# Sensor_Box_CAN_Shutter_CTRL_STM.net
KiCad netlist of a schematic drawn in Altium Designer
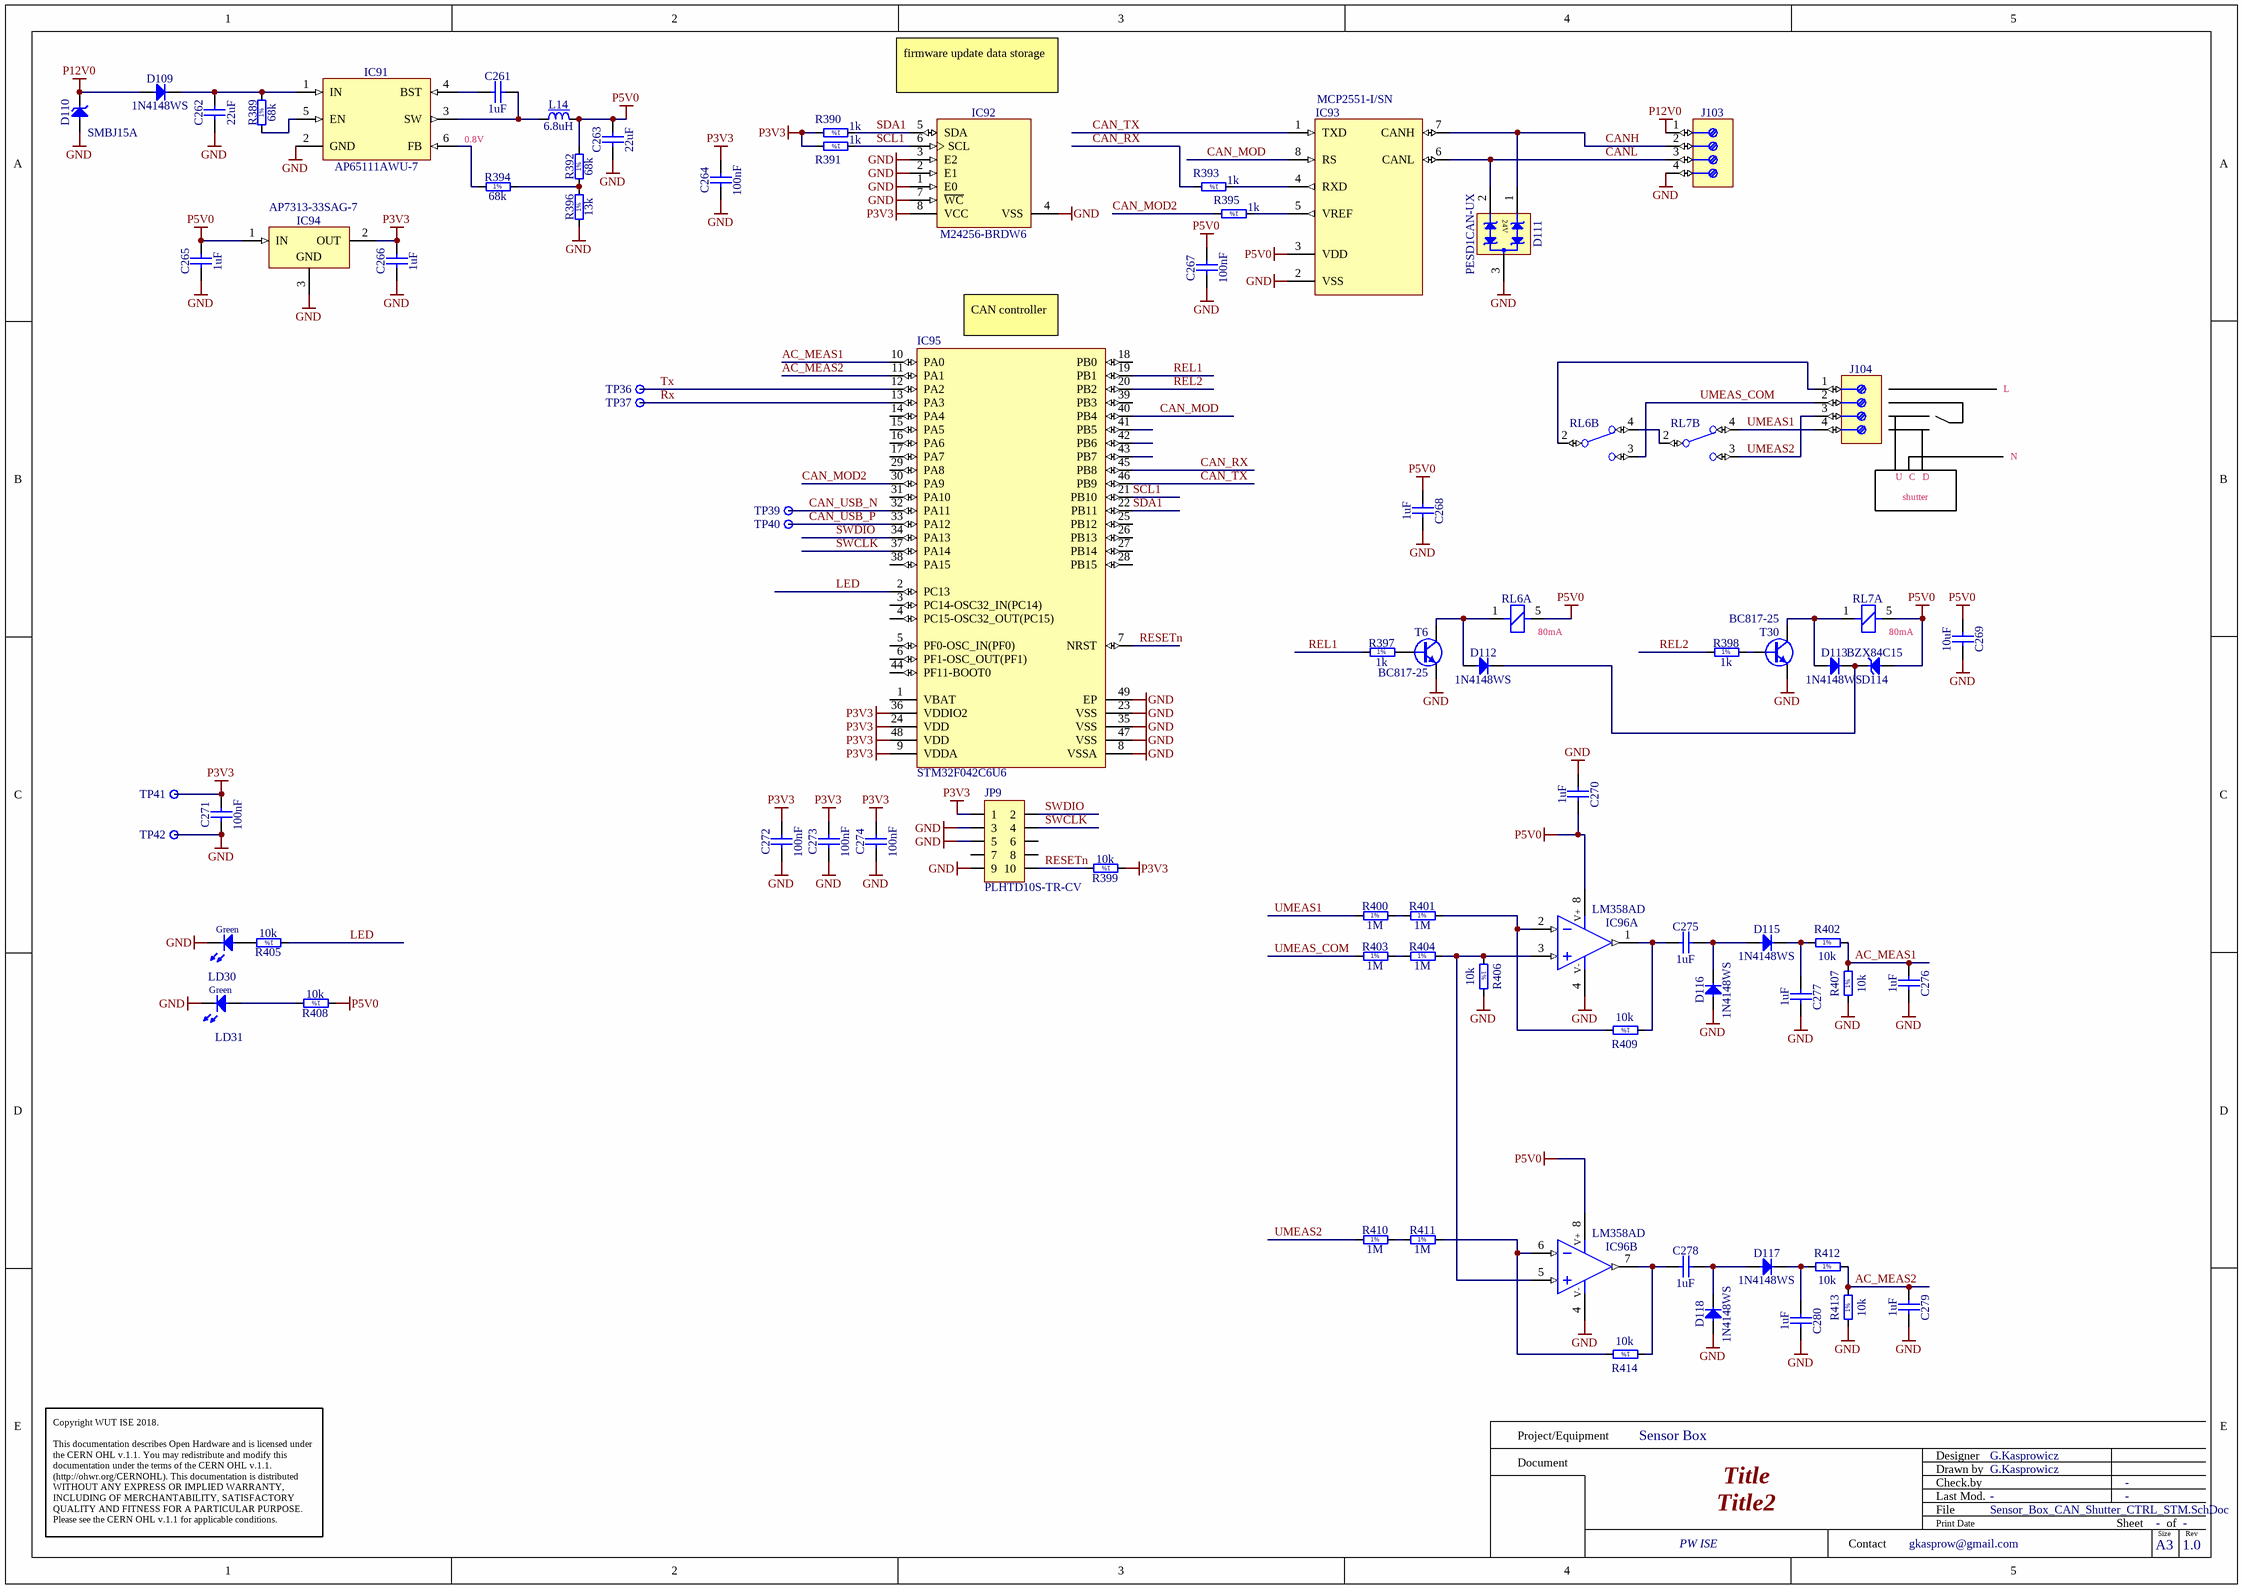
[diagram p0: Sensor_Box_CAN_Shutter_CTRL_STM.SchDoc]

(export (version "E")
  (design (tool "Eeschema 10.0.6"))
  (components
    (comp (ref "C261")
      (value "1uF")
      (footprint "CAPC1005X55N")
      (description "Non-polarised capacitor")
      (fields
        (field (name "PART NUMBER") "CC0402_1UF_16V_10%_X5R")
        (field (name "VOLTAGE") "16V")
        (field (name "AUTHOR") "CERN DEM JLC")
      )
      (libsource (lib "Capacitors") (part "Capacitor - non polarized"))
    )
    (comp (ref "C262")
      (value "22uF")
      (footprint "CAPC1709X100N")
      (description "Non-polarised capacitor")
      (fields
        (field (name "PART NUMBER") "CC0603_22UF_6.3V_20%_X5R")
        (field (name "VOLTAGE") "6.3V")
        (field (name "AUTHOR") "CERN DEM JLC")
      )
      (libsource (lib "Capacitors") (part "Capacitor - non polarized"))
    )
    (comp (ref "C263")
      (value "22uF")
      (footprint "CAPC1709X100N")
      (description "Non-polarised capacitor")
      (fields
        (field (name "PART NUMBER") "CC0603_22UF_6.3V_20%_X5R")
        (field (name "VOLTAGE") "6.3V")
        (field (name "AUTHOR") "CERN DEM JLC")
      )
      (libsource (lib "Capacitors") (part "Capacitor - non polarized"))
    )
    (comp (ref "C264")
      (value "100nF")
      (footprint "CAPC1005X55N")
      (description "Non-polarised capacitor")
      (fields
        (field (name "PART NUMBER") "CC0402_100NF_16V_10%_X5R")
        (field (name "VOLTAGE") "16V")
        (field (name "AUTHOR") "CERN DEM JLC")
      )
      (libsource (lib "Capacitors") (part "Capacitor - non polarized"))
    )
    (comp (ref "C265")
      (value "1uF")
      (footprint "CAPC1005X55N")
      (description "Non-polarised capacitor")
      (fields
        (field (name "PART NUMBER") "CC0402_1UF_16V_10%_X5R")
        (field (name "VOLTAGE") "16V")
        (field (name "AUTHOR") "CERN DEM JLC")
      )
      (libsource (lib "Capacitors") (part "Capacitor - non polarized"))
    )
    (comp (ref "C266")
      (value "1uF")
      (footprint "CAPC1005X55N")
      (description "Non-polarised capacitor")
      (fields
        (field (name "PART NUMBER") "CC0402_1UF_16V_10%_X5R")
        (field (name "VOLTAGE") "16V")
        (field (name "AUTHOR") "CERN DEM JLC")
      )
      (libsource (lib "Capacitors") (part "Capacitor - non polarized"))
    )
    (comp (ref "C267")
      (value "100nF")
      (footprint "CAPC1005X55N")
      (description "Non-polarised capacitor")
      (fields
        (field (name "PART NUMBER") "CC0402_100NF_16V_10%_X5R")
        (field (name "VOLTAGE") "16V")
        (field (name "AUTHOR") "CERN DEM JLC")
      )
      (libsource (lib "Capacitors") (part "Capacitor - non polarized"))
    )
    (comp (ref "C268")
      (value "1uF")
      (footprint "CAPC1005X55N")
      (description "Non-polarised capacitor")
      (fields
        (field (name "PART NUMBER") "CC0402_1UF_16V_10%_X5R")
        (field (name "VOLTAGE") "16V")
        (field (name "AUTHOR") "CERN DEM JLC")
      )
      (libsource (lib "Capacitors") (part "Capacitor - non polarized"))
    )
    (comp (ref "C269")
      (value "10uF")
      (footprint "CAPC2012X135N")
      (description "Non-polarised capacitor")
      (fields
        (field (name "PART NUMBER") "CC0805_10UF_16V_10%_X5R")
        (field (name "VOLTAGE") "16V")
        (field (name "AUTHOR") "CERN DEM JLC")
      )
      (libsource (lib "Capacitors") (part "Capacitor - non polarized"))
    )
    (comp (ref "C270")
      (value "1uF")
      (footprint "CAPC1005X55N")
      (description "Non-polarised capacitor")
      (fields
        (field (name "PART NUMBER") "CC0402_1UF_16V_10%_X5R")
        (field (name "VOLTAGE") "16V")
        (field (name "AUTHOR") "CERN DEM JLC")
      )
      (libsource (lib "Capacitors") (part "Capacitor - non polarized"))
    )
    (comp (ref "C271")
      (value "100nF")
      (footprint "CAPC1005X55N")
      (description "Non-polarised capacitor")
      (fields
        (field (name "PART NUMBER") "CC0402_100NF_16V_10%_X5R")
        (field (name "VOLTAGE") "16V")
        (field (name "AUTHOR") "CERN DEM JLC")
      )
      (libsource (lib "Capacitors") (part "Capacitor - non polarized"))
    )
    (comp (ref "C272")
      (value "100nF")
      (footprint "CAPC1005X55N")
      (description "Non-polarised capacitor")
      (fields
        (field (name "PART NUMBER") "CC0402_100NF_16V_10%_X5R")
        (field (name "VOLTAGE") "16V")
        (field (name "AUTHOR") "CERN DEM JLC")
      )
      (libsource (lib "Capacitors") (part "Capacitor - non polarized"))
    )
    (comp (ref "C273")
      (value "100nF")
      (footprint "CAPC1005X55N")
      (description "Non-polarised capacitor")
      (fields
        (field (name "PART NUMBER") "CC0402_100NF_16V_10%_X5R")
        (field (name "VOLTAGE") "16V")
        (field (name "AUTHOR") "CERN DEM JLC")
      )
      (libsource (lib "Capacitors") (part "Capacitor - non polarized"))
    )
    (comp (ref "C274")
      (value "100nF")
      (footprint "CAPC1005X55N")
      (description "Non-polarised capacitor")
      (fields
        (field (name "PART NUMBER") "CC0402_100NF_16V_10%_X5R")
        (field (name "VOLTAGE") "16V")
        (field (name "AUTHOR") "CERN DEM JLC")
      )
      (libsource (lib "Capacitors") (part "Capacitor - non polarized"))
    )
    (comp (ref "C275")
      (value "1uF")
      (footprint "CAPC1005X55N")
      (description "Non-polarised capacitor")
      (fields
        (field (name "PART NUMBER") "CC0402_1UF_16V_10%_X5R")
        (field (name "VOLTAGE") "16V")
        (field (name "AUTHOR") "CERN DEM JLC")
      )
      (libsource (lib "Capacitors") (part "Capacitor - non polarized"))
    )
    (comp (ref "C276")
      (value "1uF")
      (footprint "CAPC1005X55N")
      (description "Non-polarised capacitor")
      (fields
        (field (name "PART NUMBER") "CC0402_1UF_16V_10%_X5R")
        (field (name "VOLTAGE") "16V")
        (field (name "AUTHOR") "CERN DEM JLC")
      )
      (libsource (lib "Capacitors") (part "Capacitor - non polarized"))
    )
    (comp (ref "C277")
      (value "1uF")
      (footprint "CAPC1005X55N")
      (description "Non-polarised capacitor")
      (fields
        (field (name "PART NUMBER") "CC0402_1UF_16V_10%_X5R")
        (field (name "VOLTAGE") "16V")
        (field (name "AUTHOR") "CERN DEM JLC")
      )
      (libsource (lib "Capacitors") (part "Capacitor - non polarized"))
    )
    (comp (ref "C278")
      (value "1uF")
      (footprint "CAPC1005X55N")
      (description "Non-polarised capacitor")
      (fields
        (field (name "PART NUMBER") "CC0402_1UF_16V_10%_X5R")
        (field (name "VOLTAGE") "16V")
        (field (name "AUTHOR") "CERN DEM JLC")
      )
      (libsource (lib "Capacitors") (part "Capacitor - non polarized"))
    )
    (comp (ref "C279")
      (value "1uF")
      (footprint "CAPC1005X55N")
      (description "Non-polarised capacitor")
      (fields
        (field (name "PART NUMBER") "CC0402_1UF_16V_10%_X5R")
        (field (name "VOLTAGE") "16V")
        (field (name "AUTHOR") "CERN DEM JLC")
      )
      (libsource (lib "Capacitors") (part "Capacitor - non polarized"))
    )
    (comp (ref "C280")
      (value "1uF")
      (footprint "CAPC1005X55N")
      (description "Non-polarised capacitor")
      (fields
        (field (name "PART NUMBER") "CC0402_1UF_16V_10%_X5R")
        (field (name "VOLTAGE") "16V")
        (field (name "AUTHOR") "CERN DEM JLC")
      )
      (libsource (lib "Capacitors") (part "Capacitor - non polarized"))
    )
    (comp (ref "D109")
      (value "1N4148WS")
      (footprint "SODFL2512X100N")
      (description "Diode")
      (fields
        (field (name "VOLTAGE") "75V")
        (field (name "POWER") "150mA")
        (field (name "AUTHOR") "CERN DEM JLC")
      )
      (libsource (lib "ICs And Semiconductors") (part "Diode"))
    )
    (comp (ref "D110")
      (value "SMBJ15A")
      (footprint "DIOM5336X265N")
      (description "Zener Diode")
      (fields
        (field (name "VOLTAGE") "15V")
        (field (name "POWER") "600W")
        (field (name "AUTHOR") "CERN DEM JLC")
      )
      (libsource (lib "ICs And Semiconductors") (part "Diode Zener"))
    )
    (comp (ref "D111")
      (value "PESD1CAN-UX")
      (footprint "SOT95P237X112-3N")
      (description "TVS Diode for CAN")
      (fields
        (field (name "VOLTAGE") "24V")
        (field (name "POWER") "400W")
        (field (name "AUTHOR") "CERN DEM JLC")
      )
      (libsource (lib "LIBRARY_SCH") (part "D_TVS_PESD1CAN"))
    )
    (comp (ref "D112")
      (value "1N4148WS")
      (footprint "SODFL2512X100N")
      (description "Diode")
      (fields
        (field (name "VOLTAGE") "75V")
        (field (name "POWER") "150mA")
        (field (name "AUTHOR") "CERN DEM JLC")
      )
      (libsource (lib "ICs And Semiconductors") (part "Diode"))
    )
    (comp (ref "D113")
      (value "1N4148WS")
      (footprint "SODFL2512X100N")
      (description "Diode")
      (fields
        (field (name "VOLTAGE") "75V")
        (field (name "POWER") "150mA")
        (field (name "AUTHOR") "CERN DEM JLC")
      )
      (libsource (lib "ICs And Semiconductors") (part "Diode"))
    )
    (comp (ref "D114")
      (value "BZX84C15")
      (footprint "SOT95P240X130-3N")
      (description "Diode Zener Anode Pin 1 Cathode Pin 3 (Pas de pin 2)")
      (fields
        (field (name "VOLTAGE") "15V")
        (field (name "POWER") "350mW")
        (field (name "AUTHOR") "CERN DEM JLC")
      )
      (libsource (lib "ICs And Semiconductors") (part "Diode Zener A1C3"))
    )
    (comp (ref "D115")
      (value "1N4148WS")
      (footprint "SODFL2512X100N")
      (description "Diode")
      (fields
        (field (name "VOLTAGE") "75V")
        (field (name "POWER") "150mA")
        (field (name "AUTHOR") "CERN DEM JLC")
      )
      (libsource (lib "ICs And Semiconductors") (part "Diode"))
    )
    (comp (ref "D116")
      (value "1N4148WS")
      (footprint "SODFL2512X100N")
      (description "Diode")
      (fields
        (field (name "VOLTAGE") "75V")
        (field (name "POWER") "150mA")
        (field (name "AUTHOR") "CERN DEM JLC")
      )
      (libsource (lib "ICs And Semiconductors") (part "Diode"))
    )
    (comp (ref "D117")
      (value "1N4148WS")
      (footprint "SODFL2512X100N")
      (description "Diode")
      (fields
        (field (name "VOLTAGE") "75V")
        (field (name "POWER") "150mA")
        (field (name "AUTHOR") "CERN DEM JLC")
      )
      (libsource (lib "ICs And Semiconductors") (part "Diode"))
    )
    (comp (ref "D118")
      (value "1N4148WS")
      (footprint "SODFL2512X100N")
      (description "Diode")
      (fields
        (field (name "VOLTAGE") "75V")
        (field (name "POWER") "150mA")
        (field (name "AUTHOR") "CERN DEM JLC")
      )
      (libsource (lib "ICs And Semiconductors") (part "Diode"))
    )
    (comp (ref "IC91")
      (value "AP65111AWU-7")
      (footprint "SOT95P280X100-6N")
      (description "Light Load Improved 1.5A Synch DC/DC Buck Converter")
      (fields (field (name "MANUFACTURER") "DIODES INCORPORATED") (field (name "AUTHOR") "CERN DEM JLC"))
      (libsource (lib "ICs And Semiconductors") (part "AP65111A"))
    )
    (comp (ref "IC92")
      (value "M24256-BRDW6")
      (footprint "SOP65P640X120-8N")
      (description "256-Kbit Serial I²C Bus EEPROM")
      (fields
        (field (name "PART NUMBER") "M24256-BRDW6P")
        (field (name "MANUFACTURER") "ST MICROELECTRONICS")
        (field (name "AUTHOR") "CERN DEM MR")
      )
      (libsource (lib "LIBRARY_SCH") (part "MEM_M24256-BRDW6P"))
    )
    (comp (ref "IC93")
      (value "MCP2551-I/SN")
      (footprint "SOIC127P600X175-8N")
      (description "High-Speed CAN Transceiver, 8-Pin SOIC, Industrial Temperature")
      (fields (field (name "MANUFACTURER") "MICROCHIP TECHNOLOGY") (field (name "AUTHOR") "GK"))
      (libsource (lib "LIBRARY_SCH") (part "IFC_MCP2551"))
    )
    (comp (ref "IC94")
      (value "AP7313-33SAG-7")
      (footprint "SOT95P240X130-3N")
      (description "3-Terminal Regulator 1=IN 2=OUT 3=GND")
      (fields (field (name "MANUFACTURER") "DIODES INCORPORATED") (field (name "AUTHOR") "CERN DEM JLC"))
      (libsource (lib "ICs And Semiconductors") (part "REG3 1IN-2OUT-3GND"))
    )
    (comp (ref "IC95")
      (value "STM32F042C6U6")
      (footprint "STM-UFQFPN48_L")
      (libsource (lib "Altium Content Vault") (part "MC-ARM-STM32F042-UFQFPN48"))
    )
    (comp (ref "IC96")
      (value "LM358AD")
      (footprint "SOIC127P600X175-8N")
      (description "Dual Operational Amplifier")
      (fields (field (name "MANUFACTURER") "TEXAS INSTRUMENTS") (field (name "AUTHOR") "CERN DEM JLC"))
      (libsource (lib "ICs And Semiconductors") (part "Operational Amplifier x2 Type1"))
    )
    (comp (ref "J103")
      (value "~")
      (footprint "PHOENIX_1725672")
      (description "Terminal Block, 4 Positions, Screw Connection")
      (fields
        (field (name "PART NUMBER") "PHOENIX_1725672")
        (field (name "MANUFACTURER") "PHOENIX CONTACT")
        (field (name "AUTHOR") "CERN DEM JMW")
      )
      (libsource (lib "Connectors") (part "Terminal Block_4 Positions_Screw Connection"))
    )
    (comp (ref "J104")
      (value "~")
      (footprint "TYCO_282836-4")
      (description "Terminal Block, 4 Positions, Screw Connection")
      (fields
        (field (name "PART NUMBER") "TYCO_282836-4")
        (field (name "MANUFACTURER") "TYCO ELECTRONICS")
        (field (name "AUTHOR") "CERN DEM JLC")
      )
      (libsource (lib "Connectors") (part "Terminal Block_4 Positions_Screw Connection"))
    )
    (comp (ref "JP9")
      (value "PLHTD10S-TR-CV")
      (footprint "PLHTD10S-TR-CV")
      (description "1.27 mm dual row goldpin (Maritex)")
      (libsource (lib "LIBRARY_SCH") (part "CON_2x5 1.27 SMT Male"))
    )
    (comp (ref "L14")
      (value "6.8uH")
      (footprint "IND_WALSIN_WLPN3030")
      (description "6,8uH; 900mA; 0,211Ω; 3x3x1,5mm")
      (fields
        (field (name "PART NUMBER") "IND_6.8UH_20%_WALSIN_WLPN303015M6R8PB")
        (field (name "POWER") "900mA")
        (field (name "AUTHOR") "GK")
      )
      (libsource (lib "LIBRARY_SCH") (part "IND_WLPN3030"))
    )
    (comp (ref "LD30")
      (value "Green")
      (footprint "LED_KINGBRIGHT_KPH-1608CGCK")
      (description "LED Green 1C 2A")
      (fields
        (field (name "PART NUMBER") "LED_KINGBRIGHT_KPH-1608CGCK")
        (field (name "MANUFACTURER") "KINGBRIGHT")
        (field (name "AUTHOR") "CERN DEM JLC")
      )
      (libsource (lib "ICs And Semiconductors") (part "LED Green 1C 2A"))
    )
    (comp (ref "LD31")
      (value "Green")
      (footprint "LED_KINGBRIGHT_KPH-1608CGCK")
      (description "LED Green 1C 2A")
      (fields
        (field (name "PART NUMBER") "LED_KINGBRIGHT_KPH-1608CGCK")
        (field (name "MANUFACTURER") "KINGBRIGHT")
        (field (name "AUTHOR") "CERN DEM JLC")
      )
      (libsource (lib "ICs And Semiconductors") (part "LED Green 1C 2A"))
    )
    (comp (ref "R389")
      (value "68k")
      (footprint "RESC1005X40N")
      (description "Resistor - 1%")
      (fields
        (field (name "PART NUMBER") "R0402_68K_1%_0.0625W_100PPM")
        (field (name "POWER") "0.0625W")
        (field (name "AUTHOR") "CERN DEM JLC")
      )
      (libsource (lib "Resistors") (part "Resistor - 1%"))
    )
    (comp (ref "R390")
      (value "1k")
      (footprint "RESC1005X40N")
      (description "Resistor - 1%")
      (fields
        (field (name "PART NUMBER") "R0402_1K_1%_0.0625W_100PPM")
        (field (name "POWER") "0.0625W")
        (field (name "AUTHOR") "CERN DEM JLC")
      )
      (libsource (lib "Resistors") (part "Resistor - 1%"))
    )
    (comp (ref "R391")
      (value "1k")
      (footprint "RESC1005X40N")
      (description "Resistor - 1%")
      (fields
        (field (name "PART NUMBER") "R0402_1K_1%_0.0625W_100PPM")
        (field (name "POWER") "0.0625W")
        (field (name "AUTHOR") "CERN DEM JLC")
      )
      (libsource (lib "Resistors") (part "Resistor - 1%"))
    )
    (comp (ref "R392")
      (value "68k")
      (footprint "RESC1005X40N")
      (description "Resistor - 1%")
      (fields
        (field (name "PART NUMBER") "R0402_68K_1%_0.0625W_100PPM")
        (field (name "POWER") "0.0625W")
        (field (name "AUTHOR") "CERN DEM JLC")
      )
      (libsource (lib "Resistors") (part "Resistor - 1%"))
    )
    (comp (ref "R393")
      (value "1k")
      (footprint "RESC1005X40N")
      (description "Resistor - 1%")
      (fields
        (field (name "PART NUMBER") "R0402_1K_1%_0.0625W_100PPM")
        (field (name "POWER") "0.0625W")
        (field (name "AUTHOR") "CERN DEM JLC")
      )
      (libsource (lib "Resistors") (part "Resistor - 1%"))
    )
    (comp (ref "R394")
      (value "68k")
      (footprint "RESC1005X40N")
      (description "Resistor - 1%")
      (fields
        (field (name "PART NUMBER") "R0402_68K_1%_0.0625W_100PPM")
        (field (name "POWER") "0.0625W")
        (field (name "AUTHOR") "CERN DEM JLC")
      )
      (libsource (lib "Resistors") (part "Resistor - 1%"))
    )
    (comp (ref "R395")
      (value "1k")
      (footprint "RESC1005X40N")
      (description "Resistor - 1%")
      (fields
        (field (name "PART NUMBER") "R0402_1K_1%_0.0625W_100PPM")
        (field (name "POWER") "0.0625W")
        (field (name "AUTHOR") "CERN DEM JLC")
      )
      (libsource (lib "Resistors") (part "Resistor - 1%"))
    )
    (comp (ref "R396")
      (value "13k")
      (footprint "RESC1005X40N")
      (description "Resistor - 1%")
      (fields
        (field (name "PART NUMBER") "R0402_13K_1%_0.0625W_100PPM")
        (field (name "POWER") "0.0625W")
        (field (name "AUTHOR") "CERN DEM JLC")
      )
      (libsource (lib "Resistors") (part "Resistor - 1%"))
    )
    (comp (ref "R397")
      (value "1k")
      (footprint "RESC1005X40N")
      (description "Resistor - 1%")
      (fields
        (field (name "PART NUMBER") "R0402_1K_1%_0.0625W_100PPM")
        (field (name "POWER") "0.0625W")
        (field (name "AUTHOR") "CERN DEM JLC")
      )
      (libsource (lib "Resistors") (part "Resistor - 1%"))
    )
    (comp (ref "R398")
      (value "1k")
      (footprint "RESC1005X40N")
      (description "Resistor - 1%")
      (fields
        (field (name "PART NUMBER") "R0402_1K_1%_0.0625W_100PPM")
        (field (name "POWER") "0.0625W")
        (field (name "AUTHOR") "CERN DEM JLC")
      )
      (libsource (lib "Resistors") (part "Resistor - 1%"))
    )
    (comp (ref "R399")
      (value "10k")
      (footprint "RESC1005X40N")
      (description "Resistor - 1%")
      (fields
        (field (name "PART NUMBER") "R0402_10K_1%_0.0625W_100PPM")
        (field (name "POWER") "0.0625W")
        (field (name "AUTHOR") "CERN DEM JLC")
      )
      (libsource (lib "Resistors") (part "Resistor - 1%"))
    )
    (comp (ref "R400")
      (value "1M")
      (footprint "RESC3216X65N")
      (description "Resistor - 1%")
      (fields
        (field (name "PART NUMBER") "R1206_1M_1%_0.25W_100PPM")
        (field (name "POWER") "0.25W")
        (field (name "AUTHOR") "CERN DEM JLC")
      )
      (libsource (lib "Resistors") (part "Resistor - 1%"))
    )
    (comp (ref "R401")
      (value "1M")
      (footprint "RESC3216X65N")
      (description "Resistor - 1%")
      (fields
        (field (name "PART NUMBER") "R1206_1M_1%_0.25W_100PPM")
        (field (name "POWER") "0.25W")
        (field (name "AUTHOR") "CERN DEM JLC")
      )
      (libsource (lib "Resistors") (part "Resistor - 1%"))
    )
    (comp (ref "R402")
      (value "10k")
      (footprint "RESC1005X40N")
      (description "Resistor - 1%")
      (fields
        (field (name "PART NUMBER") "R0402_10K_1%_0.0625W_100PPM")
        (field (name "POWER") "0.0625W")
        (field (name "AUTHOR") "CERN DEM JLC")
      )
      (libsource (lib "Resistors") (part "Resistor - 1%"))
    )
    (comp (ref "R403")
      (value "1M")
      (footprint "RESC3216X65N")
      (description "Resistor - 1%")
      (fields
        (field (name "PART NUMBER") "R1206_1M_1%_0.25W_100PPM")
        (field (name "POWER") "0.25W")
        (field (name "AUTHOR") "CERN DEM JLC")
      )
      (libsource (lib "Resistors") (part "Resistor - 1%"))
    )
    (comp (ref "R404")
      (value "1M")
      (footprint "RESC3216X65N")
      (description "Resistor - 1%")
      (fields
        (field (name "PART NUMBER") "R1206_1M_1%_0.25W_100PPM")
        (field (name "POWER") "0.25W")
        (field (name "AUTHOR") "CERN DEM JLC")
      )
      (libsource (lib "Resistors") (part "Resistor - 1%"))
    )
    (comp (ref "R405")
      (value "10k")
      (footprint "RESC1005X40N")
      (description "Resistor - 1%")
      (fields
        (field (name "PART NUMBER") "R0402_10K_1%_0.0625W_100PPM")
        (field (name "POWER") "0.0625W")
        (field (name "AUTHOR") "CERN DEM JLC")
      )
      (libsource (lib "Resistors") (part "Resistor - 1%"))
    )
    (comp (ref "R406")
      (value "10k")
      (footprint "RESC1005X40N")
      (description "Resistor - 1%")
      (fields
        (field (name "PART NUMBER") "R0402_10K_1%_0.0625W_100PPM")
        (field (name "POWER") "0.0625W")
        (field (name "AUTHOR") "CERN DEM JLC")
      )
      (libsource (lib "Resistors") (part "Resistor - 1%"))
    )
    (comp (ref "R407")
      (value "10k")
      (footprint "RESC1005X40N")
      (description "Resistor - 1%")
      (fields
        (field (name "PART NUMBER") "R0402_10K_1%_0.0625W_100PPM")
        (field (name "POWER") "0.0625W")
        (field (name "AUTHOR") "CERN DEM JLC")
      )
      (libsource (lib "Resistors") (part "Resistor - 1%"))
    )
    (comp (ref "R408")
      (value "10k")
      (footprint "RESC1005X40N")
      (description "Resistor - 1%")
      (fields
        (field (name "PART NUMBER") "R0402_10K_1%_0.0625W_100PPM")
        (field (name "POWER") "0.0625W")
        (field (name "AUTHOR") "CERN DEM JLC")
      )
      (libsource (lib "Resistors") (part "Resistor - 1%"))
    )
    (comp (ref "R409")
      (value "10k")
      (footprint "RESC1005X40N")
      (description "Resistor - 1%")
      (fields
        (field (name "PART NUMBER") "R0402_10K_1%_0.0625W_100PPM")
        (field (name "POWER") "0.0625W")
        (field (name "AUTHOR") "CERN DEM JLC")
      )
      (libsource (lib "Resistors") (part "Resistor - 1%"))
    )
    (comp (ref "R410")
      (value "1M")
      (footprint "RESC3216X65N")
      (description "Resistor - 1%")
      (fields
        (field (name "PART NUMBER") "R1206_1M_1%_0.25W_100PPM")
        (field (name "POWER") "0.25W")
        (field (name "AUTHOR") "CERN DEM JLC")
      )
      (libsource (lib "Resistors") (part "Resistor - 1%"))
    )
    (comp (ref "R411")
      (value "1M")
      (footprint "RESC3216X65N")
      (description "Resistor - 1%")
      (fields
        (field (name "PART NUMBER") "R1206_1M_1%_0.25W_100PPM")
        (field (name "POWER") "0.25W")
        (field (name "AUTHOR") "CERN DEM JLC")
      )
      (libsource (lib "Resistors") (part "Resistor - 1%"))
    )
    (comp (ref "R412")
      (value "10k")
      (footprint "RESC1005X40N")
      (description "Resistor - 1%")
      (fields
        (field (name "PART NUMBER") "R0402_10K_1%_0.0625W_100PPM")
        (field (name "POWER") "0.0625W")
        (field (name "AUTHOR") "CERN DEM JLC")
      )
      (libsource (lib "Resistors") (part "Resistor - 1%"))
    )
    (comp (ref "R413")
      (value "10k")
      (footprint "RESC1005X40N")
      (description "Resistor - 1%")
      (fields
        (field (name "PART NUMBER") "R0402_10K_1%_0.0625W_100PPM")
        (field (name "POWER") "0.0625W")
        (field (name "AUTHOR") "CERN DEM JLC")
      )
      (libsource (lib "Resistors") (part "Resistor - 1%"))
    )
    (comp (ref "R414")
      (value "10k")
      (footprint "RESC1005X40N")
      (description "Resistor - 1%")
      (fields
        (field (name "PART NUMBER") "R0402_10K_1%_0.0625W_100PPM")
        (field (name "POWER") "0.0625W")
        (field (name "AUTHOR") "CERN DEM JLC")
      )
      (libsource (lib "Resistors") (part "Resistor - 1%"))
    )
    (comp (ref "RL6")
      (value "REL_OMRON_G5Q-1")
      (footprint "REL_OMRON_G5Q-1")
      (description "SPDT, Power Relay, 10A Switching Capacity, G5Q-1 Series")
      (fields
        (field (name "PART NUMBER") "REL_OMRON_G5Q-1-5VDC")
        (field (name "MANUFACTURER") "OMRON ELECTRONIC")
        (field (name "AUTHOR") "CERN DEM MR")
      )
      (libsource (lib "Eletro-mechanical") (part "REL_OMRON_G5Q-1"))
    )
    (comp (ref "RL7")
      (value "REL_OMRON_G5Q-1")
      (footprint "REL_OMRON_G5Q-1")
      (description "SPDT, Power Relay, 10A Switching Capacity, G5Q-1 Series")
      (fields
        (field (name "PART NUMBER") "REL_OMRON_G5Q-1-5VDC")
        (field (name "MANUFACTURER") "OMRON ELECTRONIC")
        (field (name "AUTHOR") "CERN DEM MR")
      )
      (libsource (lib "Eletro-mechanical") (part "REL_OMRON_G5Q-1"))
    )
    (comp (ref "T6")
      (value "BC817-25")
      (footprint "SOT95P230X110-3N")
      (description "NPN Transistor")
      (fields (field (name "MANUFACTURER") "NXP SEMICONDUCTORS") (field (name "AUTHOR") "CERN DEM JLC"))
      (libsource (lib "ICs And Semiconductors") (part "NPN B1 E2 C3"))
    )
    (comp (ref "T30")
      (value "BC817-25")
      (footprint "SOT95P230X110-3N")
      (description "NPN Transistor")
      (fields (field (name "MANUFACTURER") "NXP SEMICONDUCTORS") (field (name "AUTHOR") "CERN DEM JLC"))
      (libsource (lib "ICs And Semiconductors") (part "NPN B1 E2 C3"))
    )
    (comp (ref "TP36")
      (value "Test Point")
      (footprint "TPS127")
      (fields (field (name "PART NUMBER") "SMD_PAD_1.27X1.27MM") (field (name "AUTHOR") "CERN DEM JLC"))
      (libsource (lib "Eletro-mechanical") (part "Test Point"))
    )
    (comp (ref "TP37")
      (value "Test Point")
      (footprint "TPS127")
      (fields (field (name "PART NUMBER") "SMD_PAD_1.27X1.27MM") (field (name "AUTHOR") "CERN DEM JLC"))
      (libsource (lib "Eletro-mechanical") (part "Test Point"))
    )
    (comp (ref "TP39")
      (value "Test Point")
      (footprint "TPS127")
      (fields (field (name "PART NUMBER") "SMD_PAD_1.27X1.27MM") (field (name "AUTHOR") "CERN DEM JLC"))
      (libsource (lib "Eletro-mechanical") (part "Test Point"))
    )
    (comp (ref "TP40")
      (value "Test Point")
      (footprint "TPS127")
      (fields (field (name "PART NUMBER") "SMD_PAD_1.27X1.27MM") (field (name "AUTHOR") "CERN DEM JLC"))
      (libsource (lib "Eletro-mechanical") (part "Test Point"))
    )
    (comp (ref "TP41")
      (value "Test Point")
      (footprint "TPS127")
      (fields (field (name "PART NUMBER") "SMD_PAD_1.27X1.27MM") (field (name "AUTHOR") "CERN DEM JLC"))
      (libsource (lib "Eletro-mechanical") (part "Test Point"))
    )
    (comp (ref "TP42")
      (value "Test Point")
      (footprint "TPS127")
      (fields (field (name "PART NUMBER") "SMD_PAD_1.27X1.27MM") (field (name "AUTHOR") "CERN DEM JLC"))
      (libsource (lib "Eletro-mechanical") (part "Test Point"))
    )
  )
  (nets
    (net (code "1") (name "/AC_MEAS1") (class "Default")
      (node (ref "C276") (pin "1") (pinfunction "1_1") (pintype "passive"))
      (node (ref "IC95") (pin "10") (pinfunction "PA0_10") (pintype "bidirectional"))
      (node (ref "R402") (pin "2") (pinfunction "2_2") (pintype "passive"))
      (node (ref "R407") (pin "2") (pinfunction "2_2") (pintype "passive"))
    )
    (net (code "2") (name "/AC_MEAS2") (class "Default")
      (node (ref "C279") (pin "1") (pinfunction "1_1") (pintype "passive"))
      (node (ref "IC95") (pin "11") (pinfunction "PA1_11") (pintype "bidirectional"))
      (node (ref "R412") (pin "2") (pinfunction "2_2") (pintype "passive"))
      (node (ref "R413") (pin "2") (pinfunction "2_2") (pintype "passive"))
    )
    (net (code "3") (name "/CANH") (class "Default")
      (node (ref "D111") (pin "1") (pinfunction "I/O1_1") (pintype "passive"))
      (node (ref "IC93") (pin "7") (pinfunction "CANH_7") (pintype "bidirectional"))
      (node (ref "J103") (pin "2") (pinfunction "2_2") (pintype "bidirectional"))
    )
    (net (code "4") (name "/CANL") (class "Default")
      (node (ref "D111") (pin "2") (pinfunction "I/O2_2") (pintype "passive"))
      (node (ref "IC93") (pin "6") (pinfunction "CANL_6") (pintype "bidirectional"))
      (node (ref "J103") (pin "3") (pinfunction "3_3") (pintype "bidirectional"))
    )
    (net (code "5") (name "/CAN_MOD") (class "Default")
      (node (ref "IC93") (pin "8") (pinfunction "RS_8") (pintype "input"))
      (node (ref "IC95") (pin "40") (pinfunction "PB4_40") (pintype "bidirectional"))
    )
    (net (code "6") (name "/CAN_MOD2") (class "Default")
      (node (ref "IC95") (pin "30") (pinfunction "PA9_30") (pintype "bidirectional"))
      (node (ref "R395") (pin "2") (pinfunction "2_2") (pintype "passive"))
    )
    (net (code "7") (name "/CAN_RX") (class "Default")
      (node (ref "IC95") (pin "45") (pinfunction "PB8_45") (pintype "bidirectional"))
      (node (ref "R393") (pin "2") (pinfunction "2_2") (pintype "passive"))
    )
    (net (code "8") (name "/CAN_TX") (class "Default")
      (node (ref "IC93") (pin "1") (pinfunction "TXD_1") (pintype "input"))
      (node (ref "IC95") (pin "46") (pinfunction "PB9_46") (pintype "bidirectional"))
    )
    (net (code "9") (name "/CAN_USB_N") (class "Default")
      (node (ref "IC95") (pin "32") (pinfunction "PA11_32") (pintype "bidirectional"))
      (node (ref "TP39") (pin "1") (pinfunction "1_1") (pintype "bidirectional"))
    )
    (net (code "10") (name "/CAN_USB_P") (class "Default")
      (node (ref "IC95") (pin "33") (pinfunction "PA12_33") (pintype "bidirectional"))
      (node (ref "TP40") (pin "1") (pinfunction "1_1") (pintype "bidirectional"))
    )
    (net (code "11") (name "/LED") (class "Default")
      (node (ref "IC95") (pin "2") (pinfunction "PC13_2") (pintype "bidirectional"))
      (node (ref "R405") (pin "1") (pinfunction "1_1") (pintype "passive"))
    )
    (net (code "12") (name "/REL1") (class "Default")
      (node (ref "IC95") (pin "19") (pinfunction "PB1_19") (pintype "bidirectional"))
      (node (ref "R397") (pin "1") (pinfunction "1_1") (pintype "passive"))
    )
    (net (code "13") (name "/REL2") (class "Default")
      (node (ref "IC95") (pin "20") (pinfunction "PB2_20") (pintype "bidirectional"))
      (node (ref "R398") (pin "1") (pinfunction "1_1") (pintype "passive"))
    )
    (net (code "14") (name "/RESETn") (class "Default")
      (node (ref "IC95") (pin "7") (pinfunction "NRST_7") (pintype "bidirectional"))
      (node (ref "JP9") (pin "10") (pinfunction "10_10") (pintype "passive"))
      (node (ref "R399") (pin "2") (pinfunction "2_2") (pintype "passive"))
    )
    (net (code "15") (name "/Rx") (class "Default")
      (node (ref "IC95") (pin "13") (pinfunction "PA3_13") (pintype "bidirectional"))
      (node (ref "TP37") (pin "1") (pinfunction "1_1") (pintype "bidirectional"))
    )
    (net (code "16") (name "/SCL1") (class "Default")
      (node (ref "IC92") (pin "6") (pinfunction "SCL_6") (pintype "input"))
      (node (ref "IC95") (pin "21") (pinfunction "PB10_21") (pintype "bidirectional"))
      (node (ref "R391") (pin "1") (pinfunction "1_1") (pintype "passive"))
    )
    (net (code "17") (name "/SDA1") (class "Default")
      (node (ref "IC92") (pin "5") (pinfunction "SDA_5") (pintype "bidirectional"))
      (node (ref "IC95") (pin "22") (pinfunction "PB11_22") (pintype "bidirectional"))
      (node (ref "R390") (pin "1") (pinfunction "1_1") (pintype "passive"))
    )
    (net (code "18") (name "/SWCLK") (class "Default")
      (node (ref "IC95") (pin "37") (pinfunction "PA14_37") (pintype "bidirectional"))
      (node (ref "JP9") (pin "4") (pinfunction "4_4") (pintype "passive"))
    )
    (net (code "19") (name "/SWDIO") (class "Default")
      (node (ref "IC95") (pin "34") (pinfunction "PA13_34") (pintype "bidirectional"))
      (node (ref "JP9") (pin "2") (pinfunction "2_2") (pintype "passive"))
    )
    (net (code "20") (name "/Tx") (class "Default")
      (node (ref "IC95") (pin "12") (pinfunction "PA2_12") (pintype "bidirectional"))
      (node (ref "TP36") (pin "1") (pinfunction "1_1") (pintype "bidirectional"))
    )
    (net (code "21") (name "/UMEAS1") (class "Default")
      (node (ref "J104") (pin "4") (pinfunction "4_4") (pintype "bidirectional"))
      (node (ref "R400") (pin "1") (pinfunction "1_1") (pintype "passive"))
      (node (ref "RL7") (pin "4") (pinfunction "NC_4") (pintype "bidirectional"))
    )
    (net (code "22") (name "/UMEAS2") (class "Default")
      (node (ref "J104") (pin "3") (pinfunction "3_3") (pintype "bidirectional"))
      (node (ref "R410") (pin "1") (pinfunction "1_1") (pintype "passive"))
      (node (ref "RL7") (pin "3") (pinfunction "NO_3") (pintype "bidirectional"))
    )
    (net (code "23") (name "/UMEAS_COM") (class "Default")
      (node (ref "J104") (pin "2") (pinfunction "2_2") (pintype "bidirectional"))
      (node (ref "R403") (pin "1") (pinfunction "1_1") (pintype "passive"))
      (node (ref "RL6") (pin "3") (pinfunction "NO_3") (pintype "bidirectional"))
    )
    (net (code "24") (name "GND") (class "Default")
      (node (ref "C262") (pin "1") (pinfunction "1_1") (pintype "passive"))
      (node (ref "C263") (pin "1") (pinfunction "1_1") (pintype "passive"))
      (node (ref "C264") (pin "1") (pinfunction "1_1") (pintype "passive"))
      (node (ref "C265") (pin "1") (pinfunction "1_1") (pintype "passive"))
      (node (ref "C266") (pin "1") (pinfunction "1_1") (pintype "passive"))
      (node (ref "C267") (pin "1") (pinfunction "1_1") (pintype "passive"))
      (node (ref "C268") (pin "2") (pinfunction "2_2") (pintype "passive"))
      (node (ref "C269") (pin "2") (pinfunction "2_2") (pintype "passive"))
      (node (ref "C270") (pin "1") (pinfunction "1_1") (pintype "passive"))
      (node (ref "C271") (pin "1") (pinfunction "1_1") (pintype "passive"))
      (node (ref "C272") (pin "1") (pinfunction "1_1") (pintype "passive"))
      (node (ref "C273") (pin "1") (pinfunction "1_1") (pintype "passive"))
      (node (ref "C274") (pin "1") (pinfunction "1_1") (pintype "passive"))
      (node (ref "C276") (pin "2") (pinfunction "2_2") (pintype "passive"))
      (node (ref "C277") (pin "2") (pinfunction "2_2") (pintype "passive"))
      (node (ref "C279") (pin "2") (pinfunction "2_2") (pintype "passive"))
      (node (ref "C280") (pin "2") (pinfunction "2_2") (pintype "passive"))
      (node (ref "D110") (pin "2") (pinfunction "A_2") (pintype "passive"))
      (node (ref "D111") (pin "3") (pinfunction "GND_3") (pintype "passive"))
      (node (ref "D116") (pin "2") (pinfunction "A_2") (pintype "passive"))
      (node (ref "D118") (pin "2") (pinfunction "A_2") (pintype "passive"))
      (node (ref "IC91") (pin "2") (pinfunction "GND_2") (pintype "power_in"))
      (node (ref "IC92") (pin "1") (pinfunction "E0_1") (pintype "input"))
      (node (ref "IC92") (pin "2") (pinfunction "E1_2") (pintype "input"))
      (node (ref "IC92") (pin "3") (pinfunction "E2_3") (pintype "input"))
      (node (ref "IC92") (pin "4") (pinfunction "VSS_4") (pintype "power_in"))
      (node (ref "IC92") (pin "7") (pinfunction "~{WC}_7") (pintype "input"))
      (node (ref "IC93") (pin "2") (pinfunction "VSS_2") (pintype "power_in"))
      (node (ref "IC94") (pin "3") (pinfunction "GND_3") (pintype "power_in"))
      (node (ref "IC95") (pin "23") (pinfunction "VSS_23") (pintype "power_in"))
      (node (ref "IC95") (pin "35") (pinfunction "VSS_35") (pintype "power_in"))
      (node (ref "IC95") (pin "47") (pinfunction "VSS_47") (pintype "power_in"))
      (node (ref "IC95") (pin "49") (pinfunction "EP_49") (pintype "power_in"))
      (node (ref "IC95") (pin "8") (pinfunction "VSSA_8") (pintype "power_in"))
      (node (ref "IC96") (pin "4") (pinfunction "V-_4") (pintype "power_in"))
      (node (ref "J103") (pin "4") (pinfunction "4_4") (pintype "bidirectional"))
      (node (ref "JP9") (pin "3") (pinfunction "3_3") (pintype "passive"))
      (node (ref "JP9") (pin "5") (pinfunction "5_5") (pintype "passive"))
      (node (ref "JP9") (pin "9") (pinfunction "9_9") (pintype "passive"))
      (node (ref "LD30") (pin "1") (pinfunction "C_1") (pintype "passive"))
      (node (ref "LD31") (pin "1") (pinfunction "C_1") (pintype "passive"))
      (node (ref "R396") (pin "1") (pinfunction "1_1") (pintype "passive"))
      (node (ref "R406") (pin "2") (pinfunction "2_2") (pintype "passive"))
      (node (ref "R407") (pin "1") (pinfunction "1_1") (pintype "passive"))
      (node (ref "R413") (pin "1") (pinfunction "1_1") (pintype "passive"))
      (node (ref "T30") (pin "2") (pinfunction "E_2") (pintype "passive"))
      (node (ref "T6") (pin "2") (pinfunction "E_2") (pintype "passive"))
      (node (ref "TP42") (pin "1") (pinfunction "1_1") (pintype "bidirectional"))
    )
    (net (code "25") (name "Net-(D109-C)") (class "Default")
      (node (ref "C262") (pin "2") (pinfunction "2_2") (pintype "passive"))
      (node (ref "D109") (pin "1") (pinfunction "C_1") (pintype "passive"))
      (node (ref "IC91") (pin "1") (pinfunction "IN_1") (pintype "input"))
      (node (ref "R389") (pin "2") (pinfunction "2_2") (pintype "passive"))
    )
    (net (code "26") (name "Net-(D112-A)") (class "Default")
      (node (ref "D112") (pin "2") (pinfunction "A_2") (pintype "passive"))
      (node (ref "RL6") (pin "1") (pinfunction "1_1") (pintype "passive"))
      (node (ref "T6") (pin "3") (pinfunction "C_3") (pintype "passive"))
    )
    (net (code "27") (name "Net-(D112-C)") (class "Default")
      (node (ref "D112") (pin "1") (pinfunction "C_1") (pintype "passive"))
      (node (ref "D113") (pin "1") (pinfunction "C_1") (pintype "passive"))
      (node (ref "D114") (pin "3") (pinfunction "C_3") (pintype "passive"))
    )
    (net (code "28") (name "Net-(D113-A)") (class "Default")
      (node (ref "D113") (pin "2") (pinfunction "A_2") (pintype "passive"))
      (node (ref "RL7") (pin "1") (pinfunction "1_1") (pintype "passive"))
      (node (ref "T30") (pin "3") (pinfunction "C_3") (pintype "passive"))
    )
    (net (code "29") (name "Net-(D115-A)") (class "Default")
      (node (ref "C275") (pin "2") (pinfunction "2_2") (pintype "passive"))
      (node (ref "D115") (pin "2") (pinfunction "A_2") (pintype "passive"))
      (node (ref "D116") (pin "1") (pinfunction "C_1") (pintype "passive"))
    )
    (net (code "30") (name "Net-(D115-C)") (class "Default")
      (node (ref "C277") (pin "1") (pinfunction "1_1") (pintype "passive"))
      (node (ref "D115") (pin "1") (pinfunction "C_1") (pintype "passive"))
      (node (ref "R402") (pin "1") (pinfunction "1_1") (pintype "passive"))
    )
    (net (code "31") (name "Net-(D117-A)") (class "Default")
      (node (ref "C278") (pin "2") (pinfunction "2_2") (pintype "passive"))
      (node (ref "D117") (pin "2") (pinfunction "A_2") (pintype "passive"))
      (node (ref "D118") (pin "1") (pinfunction "C_1") (pintype "passive"))
    )
    (net (code "32") (name "Net-(D117-C)") (class "Default")
      (node (ref "C280") (pin "1") (pinfunction "1_1") (pintype "passive"))
      (node (ref "D117") (pin "1") (pinfunction "C_1") (pintype "passive"))
      (node (ref "R412") (pin "1") (pinfunction "1_1") (pintype "passive"))
    )
    (net (code "33") (name "Net-(IC91-BST)") (class "Default")
      (node (ref "C261") (pin "1") (pinfunction "1_1") (pintype "passive"))
      (node (ref "IC91") (pin "4") (pinfunction "BST_4") (pintype "input"))
    )
    (net (code "34") (name "Net-(IC91-EN)") (class "Default")
      (node (ref "IC91") (pin "5") (pinfunction "EN_5") (pintype "input"))
      (node (ref "R389") (pin "1") (pinfunction "1_1") (pintype "passive"))
    )
    (net (code "35") (name "Net-(IC91-FB)") (class "Default")
      (node (ref "IC91") (pin "6") (pinfunction "FB_6") (pintype "input"))
      (node (ref "R394") (pin "1") (pinfunction "1_1") (pintype "passive"))
    )
    (net (code "36") (name "Net-(IC91-SW)") (class "Default")
      (node (ref "C261") (pin "2") (pinfunction "2_2") (pintype "passive"))
      (node (ref "IC91") (pin "3") (pinfunction "SW_3") (pintype "output"))
      (node (ref "L14") (pin "1") (pinfunction "1_1") (pintype "passive"))
    )
    (net (code "37") (name "Net-(IC93-RXD)") (class "Default")
      (node (ref "IC93") (pin "4") (pinfunction "RXD_4") (pintype "output"))
      (node (ref "R393") (pin "1") (pinfunction "1_1") (pintype "passive"))
    )
    (net (code "38") (name "Net-(IC93-VREF)") (class "Default")
      (node (ref "IC93") (pin "5") (pinfunction "VREF_5") (pintype "output"))
      (node (ref "R395") (pin "1") (pinfunction "1_1") (pintype "passive"))
    )
    (net (code "39") (name "Net-(IC96A-IN+)") (class "Default")
      (node (ref "IC96") (pin "3") (pinfunction "IN+_3") (pintype "input"))
      (node (ref "IC96") (pin "5") (pinfunction "IN+_5") (pintype "input"))
      (node (ref "R404") (pin "2") (pinfunction "2_2") (pintype "passive"))
      (node (ref "R406") (pin "1") (pinfunction "1_1") (pintype "passive"))
    )
    (net (code "40") (name "Net-(IC96A-IN-)") (class "Default")
      (node (ref "IC96") (pin "2") (pinfunction "IN-_2") (pintype "input"))
      (node (ref "R401") (pin "2") (pinfunction "2_2") (pintype "passive"))
      (node (ref "R409") (pin "2") (pinfunction "2_2") (pintype "passive"))
    )
    (net (code "41") (name "Net-(IC96A-OUT)") (class "Default")
      (node (ref "C275") (pin "1") (pinfunction "1_1") (pintype "passive"))
      (node (ref "IC96") (pin "1") (pinfunction "OUT_1") (pintype "output"))
      (node (ref "R409") (pin "1") (pinfunction "1_1") (pintype "passive"))
    )
    (net (code "42") (name "Net-(IC96B-IN-)") (class "Default")
      (node (ref "IC96") (pin "6") (pinfunction "IN-_6") (pintype "input"))
      (node (ref "R411") (pin "2") (pinfunction "2_2") (pintype "passive"))
      (node (ref "R414") (pin "2") (pinfunction "2_2") (pintype "passive"))
    )
    (net (code "43") (name "Net-(IC96B-OUT)") (class "Default")
      (node (ref "C278") (pin "1") (pinfunction "1_1") (pintype "passive"))
      (node (ref "IC96") (pin "7") (pinfunction "OUT_7") (pintype "output"))
      (node (ref "R414") (pin "1") (pinfunction "1_1") (pintype "passive"))
    )
    (net (code "44") (name "Net-(LD30-A)") (class "Default")
      (node (ref "LD30") (pin "2") (pinfunction "A_2") (pintype "passive"))
      (node (ref "R405") (pin "2") (pinfunction "2_2") (pintype "passive"))
    )
    (net (code "45") (name "Net-(LD31-A)") (class "Default")
      (node (ref "LD31") (pin "2") (pinfunction "A_2") (pintype "passive"))
      (node (ref "R408") (pin "2") (pinfunction "2_2") (pintype "passive"))
    )
    (net (code "46") (name "Net-(R392-Pad1)") (class "Default")
      (node (ref "R392") (pin "1") (pinfunction "1_1") (pintype "passive"))
      (node (ref "R394") (pin "2") (pinfunction "2_2") (pintype "passive"))
      (node (ref "R396") (pin "2") (pinfunction "2_2") (pintype "passive"))
    )
    (net (code "47") (name "Net-(R400-Pad2)") (class "Default")
      (node (ref "R400") (pin "2") (pinfunction "2_2") (pintype "passive"))
      (node (ref "R401") (pin "1") (pinfunction "1_1") (pintype "passive"))
    )
    (net (code "48") (name "Net-(R403-Pad2)") (class "Default")
      (node (ref "R403") (pin "2") (pinfunction "2_2") (pintype "passive"))
      (node (ref "R404") (pin "1") (pinfunction "1_1") (pintype "passive"))
    )
    (net (code "49") (name "Net-(R410-Pad2)") (class "Default")
      (node (ref "R410") (pin "2") (pinfunction "2_2") (pintype "passive"))
      (node (ref "R411") (pin "1") (pinfunction "1_1") (pintype "passive"))
    )
    (net (code "50") (name "Net-(RL6B-C)") (class "Default")
      (node (ref "J104") (pin "1") (pinfunction "1_1") (pintype "bidirectional"))
      (node (ref "RL6") (pin "2") (pinfunction "C_2") (pintype "bidirectional"))
    )
    (net (code "51") (name "Net-(RL6B-NC)") (class "Default")
      (node (ref "RL6") (pin "4") (pinfunction "NC_4") (pintype "bidirectional"))
      (node (ref "RL7") (pin "2") (pinfunction "C_2") (pintype "bidirectional"))
    )
    (net (code "52") (name "Net-(T6-B)") (class "Default")
      (node (ref "R397") (pin "2") (pinfunction "2_2") (pintype "passive"))
      (node (ref "T6") (pin "1") (pinfunction "B_1") (pintype "passive"))
    )
    (net (code "53") (name "Net-(T30-B)") (class "Default")
      (node (ref "R398") (pin "2") (pinfunction "2_2") (pintype "passive"))
      (node (ref "T30") (pin "1") (pinfunction "B_1") (pintype "passive"))
    )
    (net (code "54") (name "P3V3") (class "Default")
      (node (ref "C264") (pin "2") (pinfunction "2_2") (pintype "passive"))
      (node (ref "C266") (pin "2") (pinfunction "2_2") (pintype "passive"))
      (node (ref "C271") (pin "2") (pinfunction "2_2") (pintype "passive"))
      (node (ref "C272") (pin "2") (pinfunction "2_2") (pintype "passive"))
      (node (ref "C273") (pin "2") (pinfunction "2_2") (pintype "passive"))
      (node (ref "C274") (pin "2") (pinfunction "2_2") (pintype "passive"))
      (node (ref "IC92") (pin "8") (pinfunction "VCC_8") (pintype "power_in"))
      (node (ref "IC94") (pin "2") (pinfunction "OUT_2") (pintype "power_in"))
      (node (ref "IC95") (pin "24") (pinfunction "VDD_24") (pintype "power_in"))
      (node (ref "IC95") (pin "36") (pinfunction "VDDIO2_36") (pintype "power_in"))
      (node (ref "IC95") (pin "48") (pinfunction "VDD_48") (pintype "power_in"))
      (node (ref "IC95") (pin "9") (pinfunction "VDDA_9") (pintype "power_in"))
      (node (ref "JP9") (pin "1") (pinfunction "1_1") (pintype "passive"))
      (node (ref "R390") (pin "2") (pinfunction "2_2") (pintype "passive"))
      (node (ref "R391") (pin "2") (pinfunction "2_2") (pintype "passive"))
      (node (ref "R399") (pin "1") (pinfunction "1_1") (pintype "passive"))
      (node (ref "TP41") (pin "1") (pinfunction "1_1") (pintype "bidirectional"))
    )
    (net (code "55") (name "P5V0") (class "Default")
      (node (ref "C263") (pin "2") (pinfunction "2_2") (pintype "passive"))
      (node (ref "C265") (pin "2") (pinfunction "2_2") (pintype "passive"))
      (node (ref "C267") (pin "2") (pinfunction "2_2") (pintype "passive"))
      (node (ref "C268") (pin "1") (pinfunction "1_1") (pintype "passive"))
      (node (ref "C269") (pin "1") (pinfunction "1_1") (pintype "passive"))
      (node (ref "C270") (pin "2") (pinfunction "2_2") (pintype "passive"))
      (node (ref "D114") (pin "1") (pinfunction "A_1") (pintype "passive"))
      (node (ref "IC93") (pin "3") (pinfunction "VDD_3") (pintype "power_in"))
      (node (ref "IC94") (pin "1") (pinfunction "IN_1") (pintype "input"))
      (node (ref "IC96") (pin "8") (pinfunction "V+_8") (pintype "power_in"))
      (node (ref "L14") (pin "2") (pinfunction "2_2") (pintype "passive"))
      (node (ref "R392") (pin "2") (pinfunction "2_2") (pintype "passive"))
      (node (ref "R408") (pin "1") (pinfunction "1_1") (pintype "passive"))
      (node (ref "RL6") (pin "5") (pinfunction "5_5") (pintype "passive"))
      (node (ref "RL7") (pin "5") (pinfunction "5_5") (pintype "passive"))
    )
    (net (code "56") (name "P12V0") (class "Default")
      (node (ref "D109") (pin "2") (pinfunction "A_2") (pintype "passive"))
      (node (ref "D110") (pin "1") (pinfunction "C_1") (pintype "passive"))
      (node (ref "J103") (pin "1") (pinfunction "1_1") (pintype "bidirectional"))
    )
    (net (code "57") (name "unconnected-(IC95-PA4-Pad14)") (class "Default")
      (node (ref "IC95") (pin "14") (pinfunction "PA4_14") (pintype "bidirectional"))
    )
    (net (code "58") (name "unconnected-(IC95-PA5-Pad15)") (class "Default")
      (node (ref "IC95") (pin "15") (pinfunction "PA5_15") (pintype "bidirectional"))
    )
    (net (code "59") (name "unconnected-(IC95-PA6-Pad16)") (class "Default")
      (node (ref "IC95") (pin "16") (pinfunction "PA6_16") (pintype "bidirectional"))
    )
    (net (code "60") (name "unconnected-(IC95-PA7-Pad17)") (class "Default")
      (node (ref "IC95") (pin "17") (pinfunction "PA7_17") (pintype "bidirectional"))
    )
    (net (code "61") (name "unconnected-(IC95-PA8-Pad29)") (class "Default")
      (node (ref "IC95") (pin "29") (pinfunction "PA8_29") (pintype "bidirectional"))
    )
    (net (code "62") (name "unconnected-(IC95-PA10-Pad31)") (class "Default")
      (node (ref "IC95") (pin "31") (pinfunction "PA10_31") (pintype "bidirectional"))
    )
    (net (code "63") (name "unconnected-(IC95-PA15-Pad38)") (class "Default")
      (node (ref "IC95") (pin "38") (pinfunction "PA15_38") (pintype "bidirectional"))
    )
    (net (code "64") (name "unconnected-(IC95-PB0-Pad18)") (class "Default")
      (node (ref "IC95") (pin "18") (pinfunction "PB0_18") (pintype "bidirectional"))
    )
    (net (code "65") (name "unconnected-(IC95-PB3-Pad39)") (class "Default")
      (node (ref "IC95") (pin "39") (pinfunction "PB3_39") (pintype "bidirectional"))
    )
    (net (code "66") (name "unconnected-(IC95-PB5-Pad41)") (class "Default")
      (node (ref "IC95") (pin "41") (pinfunction "PB5_41") (pintype "bidirectional"))
    )
    (net (code "67") (name "unconnected-(IC95-PB6-Pad42)") (class "Default")
      (node (ref "IC95") (pin "42") (pinfunction "PB6_42") (pintype "bidirectional"))
    )
    (net (code "68") (name "unconnected-(IC95-PB7-Pad43)") (class "Default")
      (node (ref "IC95") (pin "43") (pinfunction "PB7_43") (pintype "bidirectional"))
    )
    (net (code "69") (name "unconnected-(IC95-PB12-Pad25)") (class "Default")
      (node (ref "IC95") (pin "25") (pinfunction "PB12_25") (pintype "bidirectional"))
    )
    (net (code "70") (name "unconnected-(IC95-PB13-Pad26)") (class "Default")
      (node (ref "IC95") (pin "26") (pinfunction "PB13_26") (pintype "bidirectional"))
    )
    (net (code "71") (name "unconnected-(IC95-PB14-Pad27)") (class "Default")
      (node (ref "IC95") (pin "27") (pinfunction "PB14_27") (pintype "bidirectional"))
    )
    (net (code "72") (name "unconnected-(IC95-PB15-Pad28)") (class "Default")
      (node (ref "IC95") (pin "28") (pinfunction "PB15_28") (pintype "bidirectional"))
    )
    (net (code "73") (name "unconnected-(IC95-PC14-OSC32_IN(PC14)-Pad3)") (class "Default")
      (node (ref "IC95") (pin "3") (pinfunction "PC14-OSC32_IN(PC14)_3") (pintype "bidirectional"))
    )
    (net (code "74") (name "unconnected-(IC95-PC15-OSC32_OUT(PC15)-Pad4)") (class "Default")
      (node (ref "IC95") (pin "4") (pinfunction "PC15-OSC32_OUT(PC15)_4") (pintype "bidirectional"))
    )
    (net (code "75") (name "unconnected-(IC95-PF0-OSC_IN(PF0)-Pad5)") (class "Default")
      (node (ref "IC95") (pin "5") (pinfunction "PF0-OSC_IN(PF0)_5") (pintype "bidirectional"))
    )
    (net (code "76") (name "unconnected-(IC95-PF1-OSC_OUT(PF1)-Pad6)") (class "Default")
      (node (ref "IC95") (pin "6") (pinfunction "PF1-OSC_OUT(PF1)_6") (pintype "bidirectional"))
    )
    (net (code "77") (name "unconnected-(IC95-PF11-BOOT0-Pad44)") (class "Default")
      (node (ref "IC95") (pin "44") (pinfunction "PF11-BOOT0_44") (pintype "bidirectional"))
    )
    (net (code "78") (name "unconnected-(IC95-VBAT-Pad1)") (class "Default")
      (node (ref "IC95") (pin "1") (pinfunction "VBAT_1") (pintype "power_in"))
    )
    (net (code "79") (name "unconnected-(JP9-Pad6)") (class "Default")
      (node (ref "JP9") (pin "6") (pinfunction "6_6") (pintype "passive"))
    )
    (net (code "80") (name "unconnected-(JP9-Pad7)") (class "Default")
      (node (ref "JP9") (pin "7") (pinfunction "7_7") (pintype "passive"))
    )
    (net (code "81") (name "unconnected-(JP9-Pad8)") (class "Default")
      (node (ref "JP9") (pin "8") (pinfunction "8_8") (pintype "passive"))
    )
  )
)
